# RFDuino_I2C_V5.net
KiCad netlist of a schematic drawn in EAGLE
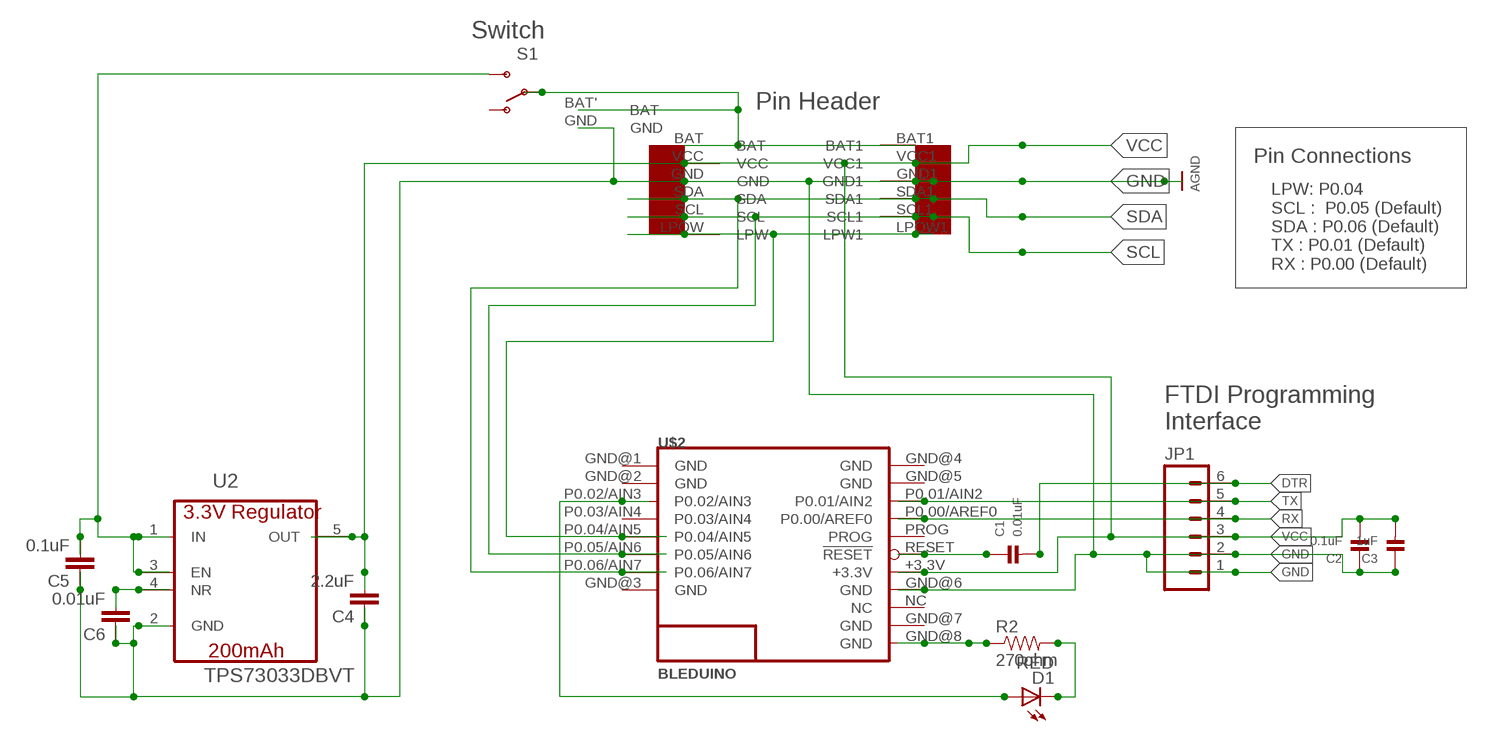
[diagram p0: schematic, sheet 1]

(export (version "E")
  (design (tool "Eeschema 10.0.6"))
  (components
    (comp (ref "C1")
      (value "0.01uF")
      (footprint "eagle-import:0402")
      (libsource (lib "eagle-import") (part "CAP_CERAMIC0402"))
    )
    (comp (ref "C2")
      (value "0.1uF")
      (footprint "eagle-import:0402")
      (libsource (lib "eagle-import") (part "CAP_CERAMIC0402"))
    )
    (comp (ref "C3")
      (value "1uF")
      (footprint "eagle-import:0402")
      (libsource (lib "eagle-import") (part "CAP_CERAMIC0402"))
    )
    (comp (ref "C4")
      (value "2.2uF")
      (footprint "eagle-import:0402-CAP")
      (libsource (lib "eagle-import") (part "CAP0402-CAP"))
    )
    (comp (ref "C5")
      (value "0.1uF")
      (footprint "eagle-import:0402-CAP")
      (libsource (lib "eagle-import") (part "CAP0402-CAP"))
    )
    (comp (ref "C6")
      (value "0.01uF")
      (footprint "eagle-import:0402-CAP")
      (libsource (lib "eagle-import") (part "CAP0402-CAP"))
    )
    (comp (ref "D1")
      (value "RED")
      (footprint "eagle-import:LED-0603")
      (libsource (lib "eagle-import") (part "LED-RED0603"))
    )
    (comp (ref "JP1")
      (value "M06SIP")
      (footprint "eagle-import:1X06")
      (libsource (lib "eagle-import") (part "M06SIP"))
    )
    (comp (ref "R2")
      (value "270ohm")
      (footprint "eagle-import:0402-RES")
      (libsource (lib "eagle-import") (part "RESISTOR0402-RES"))
    )
    (comp (ref "S1")
      (value "SWITCH-SPDT-SMD-A")
      (footprint "eagle-import:SWITCH-SPST-SMD-A")
      (libsource (lib "eagle-import") (part "SWITCH-SPDT-SMD-A"))
    )
    (comp (ref "U$1")
      (value "EZ-I2CHEADERV1")
      (footprint "eagle-import:EZ-I2CHEADERV1")
      (libsource (lib "eagle-import") (part "EZ-I2CHEADERV1"))
    )
    (comp (ref "U$2")
      (value "BLEDUINO")
      (footprint "eagle-import:BLEDUINO")
      (libsource (lib "eagle-import") (part "BLEDUINO"))
    )
    (comp (ref "U$4")
      (value "MINI_BATTERY_HOLES")
      (footprint "eagle-import:MINI_BATTERY_HOLES")
      (libsource (lib "eagle-import") (part "MINI_BATTERY_HOLES"))
    )
    (comp (ref "U2")
      (value "TPS73033DBVT")
      (footprint "eagle-import:SOT95P290X145-5N")
      (libsource (lib "eagle-import") (part "TPS73033DBVT"))
    )
  )
  (nets
    (net (code "1") (name "DTR") (class "Default")
      (node (ref "C1") (pin "2") (pinfunction "P$2_2") (pintype "passive"))
      (node (ref "JP1") (pin "6") (pinfunction "6_6") (pintype "passive"))
    )
    (net (code "2") (name "GND") (class "Default")
      (node (ref "C2") (pin "1") (pinfunction "P$1_1") (pintype "passive"))
      (node (ref "C3") (pin "1") (pinfunction "P$1_1") (pintype "passive"))
      (node (ref "C4") (pin "1") (pinfunction "1_1") (pintype "passive"))
      (node (ref "C5") (pin "1") (pinfunction "1_1") (pintype "passive"))
      (node (ref "C6") (pin "1") (pinfunction "1_1") (pintype "passive"))
      (node (ref "JP1") (pin "1") (pinfunction "1_1") (pintype "passive"))
      (node (ref "JP1") (pin "2") (pinfunction "2_2") (pintype "passive"))
      (node (ref "U$1") (pin "GND") (pinfunction "GND_GND") (pintype "bidirectional"))
      (node (ref "U$1") (pin "GND1") (pinfunction "GND1_GND1") (pintype "bidirectional"))
      (node (ref "U$2") (pin "GND@6") (pinfunction "GND_GND@6") (pintype "bidirectional"))
      (node (ref "U$4") (pin "GND") (pinfunction "GND_GND") (pintype "bidirectional"))
      (node (ref "U2") (pin "2") (pinfunction "GND_2") (pintype "passive"))
    )
    (net (code "3") (name "Net-(C1-P$1)") (class "Default")
      (node (ref "C1") (pin "1") (pinfunction "P$1_1") (pintype "passive"))
      (node (ref "U$2") (pin "RESET") (pinfunction "~{RESET}_RESET") (pintype "bidirectional"))
    )
    (net (code "4") (name "Net-(D1-PadA)") (class "Default")
      (node (ref "D1") (pin "A") (pinfunction "A_A") (pintype "passive"))
      (node (ref "U$2") (pin "P0.02/AIN3") (pinfunction "P0.02/AIN3_P0.02/AIN3") (pintype "bidirectional"))
    )
    (net (code "5") (name "Net-(D1-PadC)") (class "Default")
      (node (ref "D1") (pin "C") (pinfunction "C_C") (pintype "passive"))
      (node (ref "R2") (pin "2") (pinfunction "2_2") (pintype "passive"))
    )
    (net (code "6") (name "Net-(R2-Pad1)") (class "Default")
      (node (ref "R2") (pin "1") (pinfunction "1_1") (pintype "passive"))
      (node (ref "U$2") (pin "GND@8") (pinfunction "GND_GND@8") (pintype "bidirectional"))
    )
    (net (code "7") (name "Net-(S1-P)") (class "Default")
      (node (ref "S1") (pin "2") (pinfunction "P_2") (pintype "passive"))
      (node (ref "U$1") (pin "BAT") (pinfunction "BAT_BAT") (pintype "bidirectional"))
      (node (ref "U$1") (pin "BAT1") (pinfunction "BAT1_BAT1") (pintype "bidirectional"))
      (node (ref "U$4") (pin "BAT'") (pinfunction "BAT_BAT'") (pintype "bidirectional"))
    )
    (net (code "8") (name "Net-(S1-S)") (class "Default")
      (node (ref "C5") (pin "2") (pinfunction "2_2") (pintype "passive"))
      (node (ref "S1") (pin "3") (pinfunction "S_3") (pintype "passive"))
      (node (ref "U2") (pin "1") (pinfunction "IN_1") (pintype "input"))
      (node (ref "U2") (pin "3") (pinfunction "EN_3") (pintype "input"))
    )
    (net (code "9") (name "Net-(U$1-LPW)") (class "Default")
      (node (ref "U$1") (pin "LPOW") (pinfunction "LPW_LPOW") (pintype "bidirectional"))
      (node (ref "U$1") (pin "LPOW1") (pinfunction "LPW1_LPOW1") (pintype "bidirectional"))
      (node (ref "U$2") (pin "P0.04/AIN5") (pinfunction "P0.04/AIN5_P0.04/AIN5") (pintype "bidirectional"))
    )
    (net (code "10") (name "Net-(U2-NR)") (class "Default")
      (node (ref "C6") (pin "2") (pinfunction "2_2") (pintype "passive"))
      (node (ref "U2") (pin "4") (pinfunction "NR_4") (pintype "input"))
    )
    (net (code "11") (name "RX") (class "Default")
      (node (ref "JP1") (pin "4") (pinfunction "4_4") (pintype "passive"))
      (node (ref "U$2") (pin "P0.00/AREF0") (pinfunction "P0.00/AREF0_P0.00/AREF0") (pintype "bidirectional"))
    )
    (net (code "12") (name "SCL") (class "Default")
      (node (ref "U$1") (pin "SCL") (pinfunction "SCL_SCL") (pintype "bidirectional"))
      (node (ref "U$1") (pin "SCL1") (pinfunction "SCL1_SCL1") (pintype "bidirectional"))
      (node (ref "U$2") (pin "P0.05/AIN6") (pinfunction "P0.05/AIN6_P0.05/AIN6") (pintype "bidirectional"))
    )
    (net (code "13") (name "SDA") (class "Default")
      (node (ref "U$1") (pin "SDA") (pinfunction "SDA_SDA") (pintype "bidirectional"))
      (node (ref "U$1") (pin "SDA1") (pinfunction "SDA1_SDA1") (pintype "bidirectional"))
      (node (ref "U$2") (pin "P0.06/AIN7") (pinfunction "P0.06/AIN7_P0.06/AIN7") (pintype "bidirectional"))
    )
    (net (code "14") (name "TX") (class "Default")
      (node (ref "JP1") (pin "5") (pinfunction "5_5") (pintype "passive"))
      (node (ref "U$2") (pin "P0.01/AIN2") (pinfunction "P0.01/AIN2_P0.01/AIN2") (pintype "bidirectional"))
    )
    (net (code "15") (name "VCC") (class "Default")
      (node (ref "C2") (pin "2") (pinfunction "P$2_2") (pintype "passive"))
      (node (ref "C3") (pin "2") (pinfunction "P$2_2") (pintype "passive"))
      (node (ref "C4") (pin "2") (pinfunction "2_2") (pintype "passive"))
      (node (ref "JP1") (pin "3") (pinfunction "3_3") (pintype "passive"))
      (node (ref "U$1") (pin "VCC") (pinfunction "VCC_VCC") (pintype "bidirectional"))
      (node (ref "U$1") (pin "VCC1") (pinfunction "VCC1_VCC1") (pintype "bidirectional"))
      (node (ref "U$2") (pin "+3.3V") (pinfunction "+3.3V_+3.3V") (pintype "bidirectional"))
      (node (ref "U2") (pin "5") (pinfunction "OUT_5") (pintype "output"))
    )
    (net (code "16") (name "unconnected-(S1-O-Pad1)") (class "Default")
      (node (ref "S1") (pin "1") (pinfunction "O_1") (pintype "passive"))
    )
    (net (code "17") (name "unconnected-(U$2-GND-PadGND@1)") (class "Default")
      (node (ref "U$2") (pin "GND@1") (pinfunction "GND_GND@1") (pintype "bidirectional"))
    )
    (net (code "18") (name "unconnected-(U$2-GND-PadGND@2)") (class "Default")
      (node (ref "U$2") (pin "GND@2") (pinfunction "GND_GND@2") (pintype "bidirectional"))
    )
    (net (code "19") (name "unconnected-(U$2-GND-PadGND@3)") (class "Default")
      (node (ref "U$2") (pin "GND@3") (pinfunction "GND_GND@3") (pintype "bidirectional"))
    )
    (net (code "20") (name "unconnected-(U$2-GND-PadGND@4)") (class "Default")
      (node (ref "U$2") (pin "GND@4") (pinfunction "GND_GND@4") (pintype "bidirectional"))
    )
    (net (code "21") (name "unconnected-(U$2-GND-PadGND@5)") (class "Default")
      (node (ref "U$2") (pin "GND@5") (pinfunction "GND_GND@5") (pintype "bidirectional"))
    )
    (net (code "22") (name "unconnected-(U$2-GND-PadGND@7)") (class "Default")
      (node (ref "U$2") (pin "GND@7") (pinfunction "GND_GND@7") (pintype "bidirectional"))
    )
    (net (code "23") (name "unconnected-(U$2-PadNC)") (class "Default")
      (node (ref "U$2") (pin "NC") (pinfunction "NC_NC") (pintype "no_connect"))
    )
    (net (code "24") (name "unconnected-(U$2-PadP0.03{slash}AIN4)") (class "Default")
      (node (ref "U$2") (pin "P0.03/AIN4") (pinfunction "P0.03/AIN4_P0.03/AIN4") (pintype "bidirectional"))
    )
    (net (code "25") (name "unconnected-(U$2-PadPROG)") (class "Default")
      (node (ref "U$2") (pin "PROG") (pinfunction "PROG_PROG") (pintype "bidirectional"))
    )
  )
)
